# Voltage_Translator.net
KiCad netlist of a schematic drawn in Altium Designer
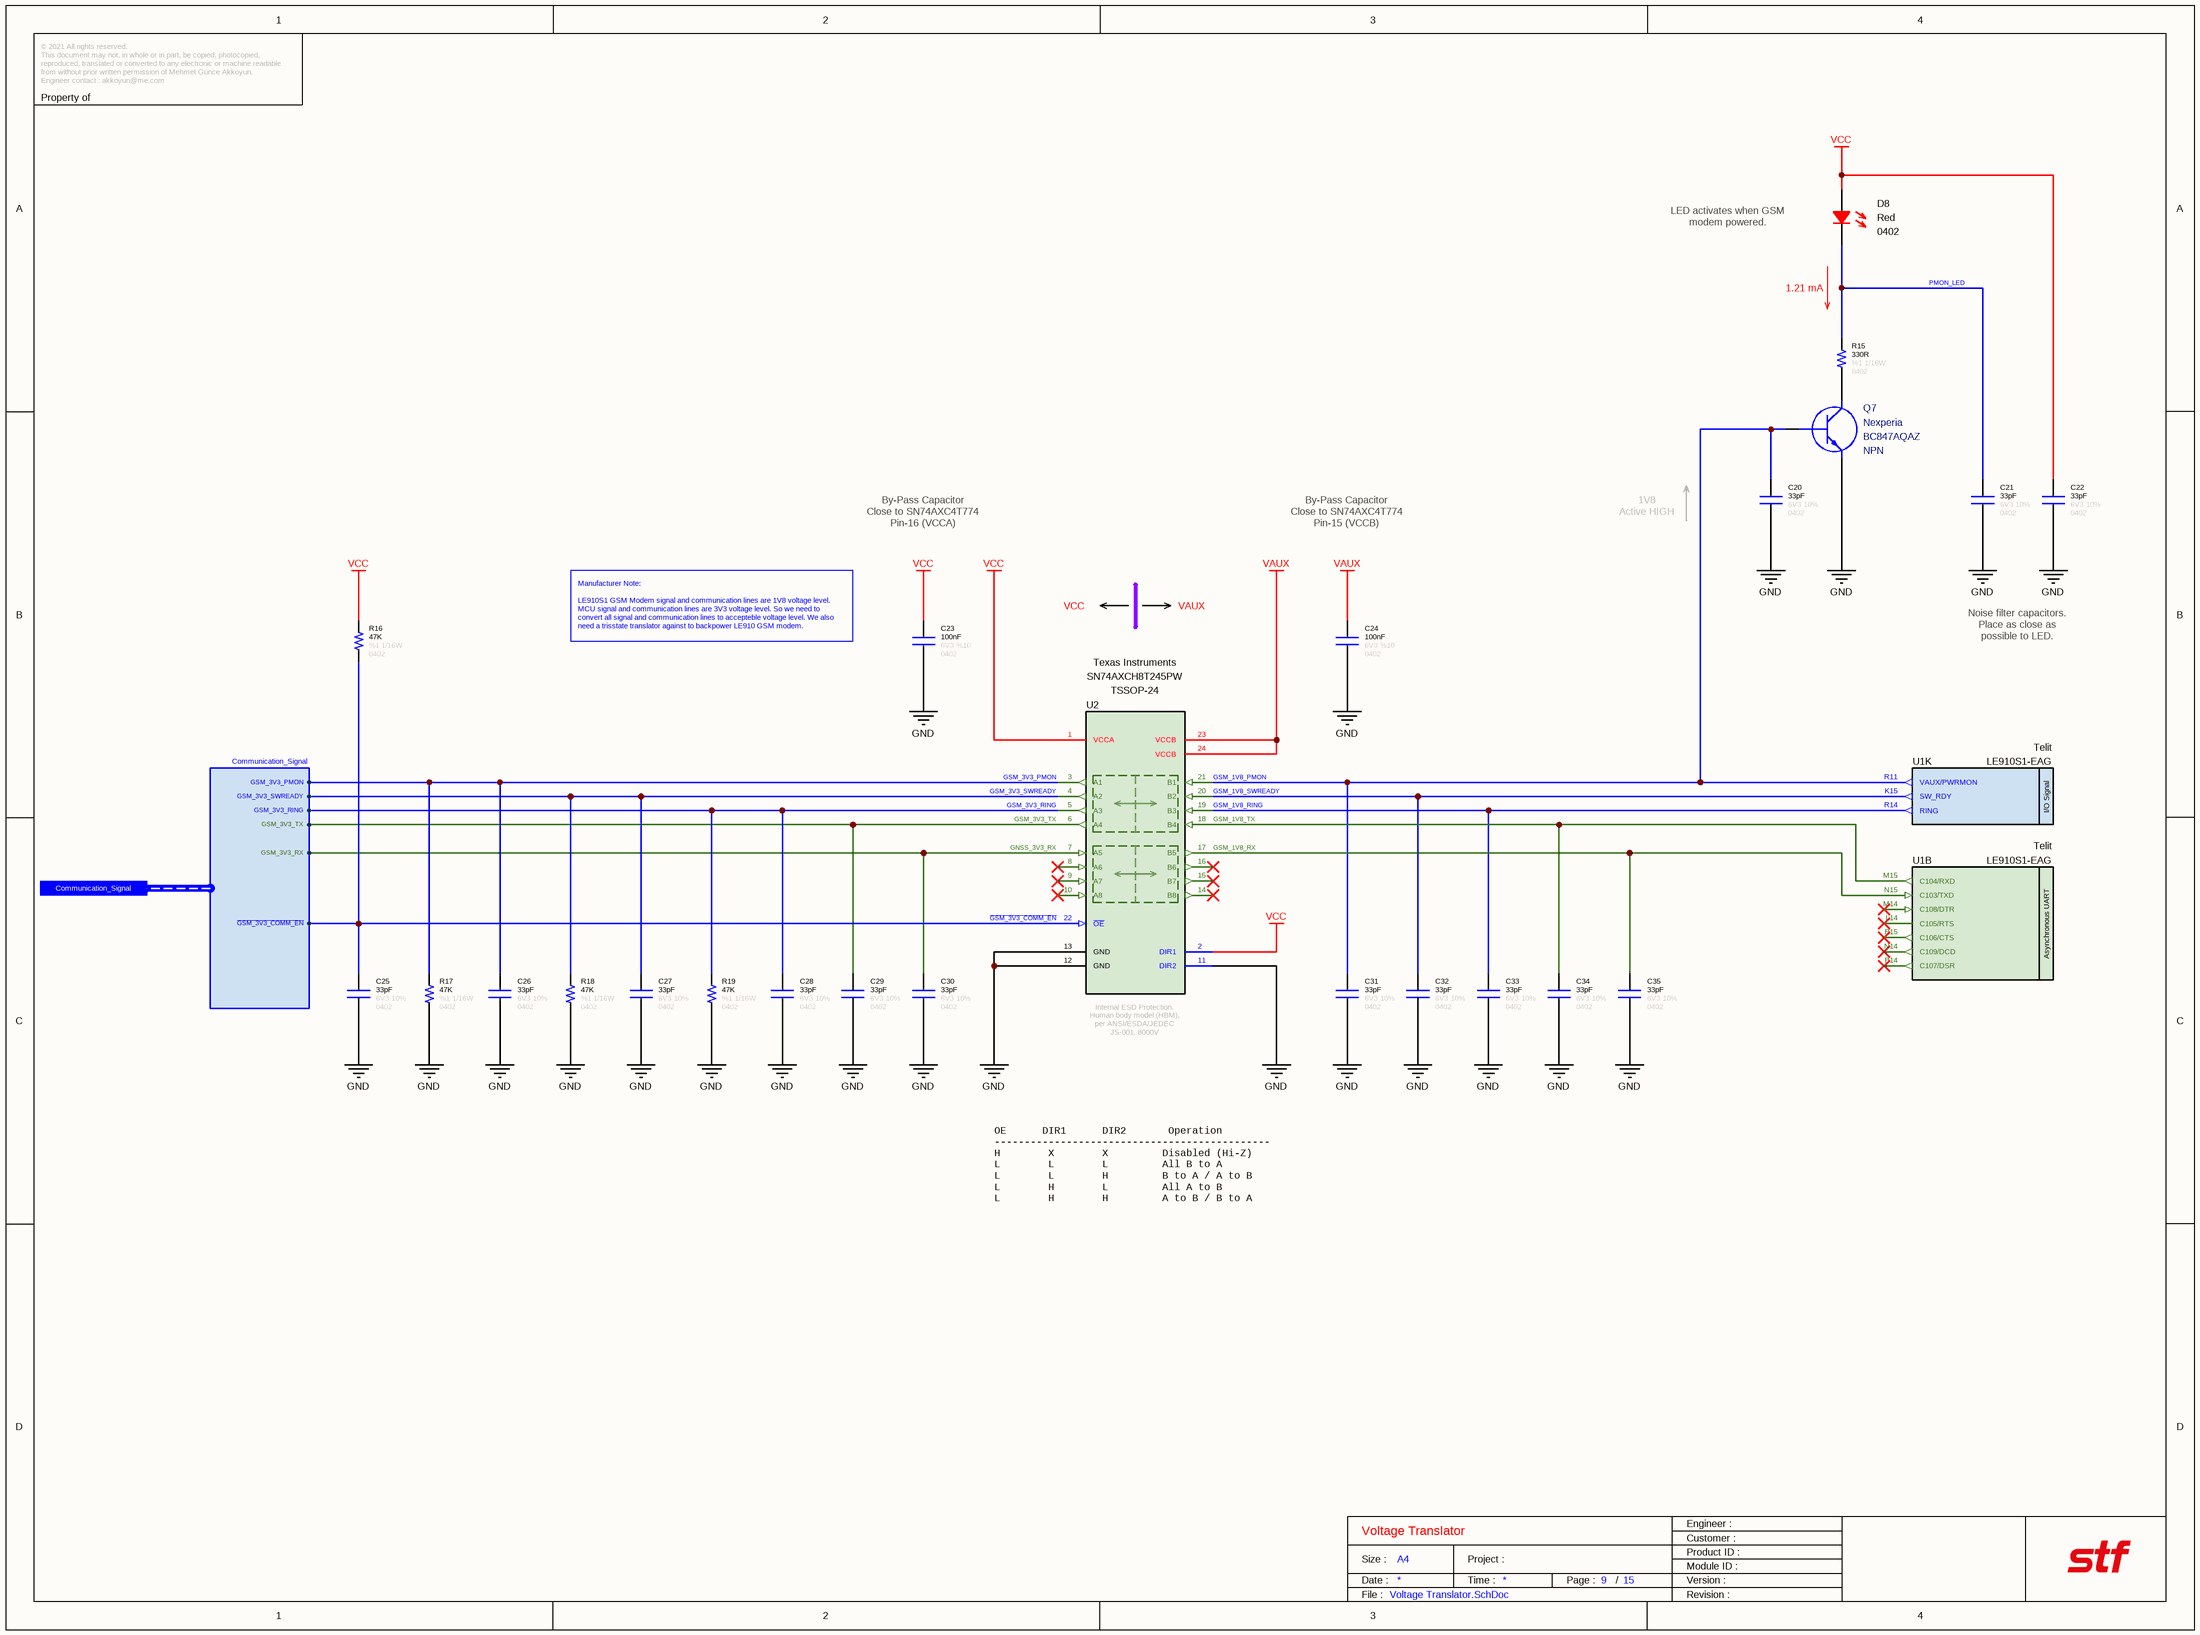
[diagram p0: Voltage Translator.SchDoc]

(export (version "E")
  (design (tool "Eeschema 10.0.6"))
  (components
    (comp (ref "C20")
      (value "33pF")
      (footprint "CAPACITOR_0402")
      (description "Capacitor - 33pF [0402] (Ceramic)")
      (fields
        (field (name "MANUFACTURER PART NUMBER") "C0402C330J9RACAUTO")
        (field (name "TOLERANCE") "10%")
        (field (name "CASE") "0402")
        (field (name "VOLTAGE") "6V3")
      )
      (libsource (lib "P101DA_Library") (part "Capacitor - 33pF [0402-6V3]"))
    )
    (comp (ref "C21")
      (value "33pF")
      (footprint "CAPACITOR_0402")
      (description "Capacitor - 33pF [0402] (Ceramic)")
      (fields
        (field (name "MANUFACTURER PART NUMBER") "C0402C330J9RACAUTO")
        (field (name "TOLERANCE") "10%")
        (field (name "CASE") "0402")
        (field (name "VOLTAGE") "6V3")
      )
      (libsource (lib "P101DA_Library") (part "Capacitor - 33pF [0402-6V3]"))
    )
    (comp (ref "C22")
      (value "33pF")
      (footprint "CAPACITOR_0402")
      (description "Capacitor - 33pF [0402] (Ceramic)")
      (fields
        (field (name "MANUFACTURER PART NUMBER") "C0402C330J9RACAUTO")
        (field (name "TOLERANCE") "10%")
        (field (name "CASE") "0402")
        (field (name "VOLTAGE") "6V3")
      )
      (libsource (lib "P101DA_Library") (part "Capacitor - 33pF [0402-6V3]"))
    )
    (comp (ref "C23")
      (value "100nF")
      (footprint "CAPACITOR_0402")
      (description "Capacitor - 100nF [0402-6V3] (Ceramic)")
      (fields
        (field (name "MANUFACTURER PART NUMBER") "04026D104KAT4A")
        (field (name "TOLERANCE") "%10")
        (field (name "VOLTAGE") "6V3")
        (field (name "CASE") "0402")
        (field (name "Comment") "Capacitor - 100nF [0402] (Ceramic)")
      )
      (libsource (lib "P101DA_Library") (part "Capacitor - 100nF [0402-6V3]"))
    )
    (comp (ref "C24")
      (value "100nF")
      (footprint "CAPACITOR_0402")
      (description "Capacitor - 100nF [0402-6V3] (Ceramic)")
      (fields
        (field (name "MANUFACTURER PART NUMBER") "04026D104KAT4A")
        (field (name "TOLERANCE") "%10")
        (field (name "VOLTAGE") "6V3")
        (field (name "CASE") "0402")
        (field (name "Comment") "Capacitor - 100nF [0402] (Ceramic)")
      )
      (libsource (lib "P101DA_Library") (part "Capacitor - 100nF [0402-6V3]"))
    )
    (comp (ref "C25")
      (value "33pF")
      (footprint "CAPACITOR_0402")
      (description "Capacitor - 33pF [0402] (Ceramic)")
      (fields
        (field (name "MANUFACTURER PART NUMBER") "C0402C330J9RACAUTO")
        (field (name "TOLERANCE") "10%")
        (field (name "CASE") "0402")
        (field (name "VOLTAGE") "6V3")
      )
      (libsource (lib "P101DA_Library") (part "Capacitor - 33pF [0402-6V3]"))
    )
    (comp (ref "C26")
      (value "33pF")
      (footprint "CAPACITOR_0402")
      (description "Capacitor - 33pF [0402] (Ceramic)")
      (fields
        (field (name "MANUFACTURER PART NUMBER") "C0402C330J9RACAUTO")
        (field (name "TOLERANCE") "10%")
        (field (name "CASE") "0402")
        (field (name "VOLTAGE") "6V3")
      )
      (libsource (lib "P101DA_Library") (part "Capacitor - 33pF [0402-6V3]"))
    )
    (comp (ref "C27")
      (value "33pF")
      (footprint "CAPACITOR_0402")
      (description "Capacitor - 33pF [0402] (Ceramic)")
      (fields
        (field (name "MANUFACTURER PART NUMBER") "C0402C330J9RACAUTO")
        (field (name "TOLERANCE") "10%")
        (field (name "CASE") "0402")
        (field (name "VOLTAGE") "6V3")
      )
      (libsource (lib "P101DA_Library") (part "Capacitor - 33pF [0402-6V3]"))
    )
    (comp (ref "C28")
      (value "33pF")
      (footprint "CAPACITOR_0402")
      (description "Capacitor - 33pF [0402] (Ceramic)")
      (fields
        (field (name "MANUFACTURER PART NUMBER") "C0402C330J9RACAUTO")
        (field (name "TOLERANCE") "10%")
        (field (name "CASE") "0402")
        (field (name "VOLTAGE") "6V3")
      )
      (libsource (lib "P101DA_Library") (part "Capacitor - 33pF [0402-6V3]"))
    )
    (comp (ref "C29")
      (value "33pF")
      (footprint "CAPACITOR_0402")
      (description "Capacitor - 33pF [0402] (Ceramic)")
      (fields
        (field (name "MANUFACTURER PART NUMBER") "C0402C330J9RACAUTO")
        (field (name "TOLERANCE") "10%")
        (field (name "CASE") "0402")
        (field (name "VOLTAGE") "6V3")
      )
      (libsource (lib "P101DA_Library") (part "Capacitor - 33pF [0402-6V3]"))
    )
    (comp (ref "C30")
      (value "33pF")
      (footprint "CAPACITOR_0402")
      (description "Capacitor - 33pF [0402] (Ceramic)")
      (fields
        (field (name "MANUFACTURER PART NUMBER") "C0402C330J9RACAUTO")
        (field (name "TOLERANCE") "10%")
        (field (name "CASE") "0402")
        (field (name "VOLTAGE") "6V3")
      )
      (libsource (lib "P101DA_Library") (part "Capacitor - 33pF [0402-6V3]"))
    )
    (comp (ref "C31")
      (value "33pF")
      (footprint "CAPACITOR_0402")
      (description "Capacitor - 33pF [0402] (Ceramic)")
      (fields
        (field (name "MANUFACTURER PART NUMBER") "C0402C330J9RACAUTO")
        (field (name "TOLERANCE") "10%")
        (field (name "CASE") "0402")
        (field (name "VOLTAGE") "6V3")
      )
      (libsource (lib "P101DA_Library") (part "Capacitor - 33pF [0402-6V3]"))
    )
    (comp (ref "C32")
      (value "33pF")
      (footprint "CAPACITOR_0402")
      (description "Capacitor - 33pF [0402] (Ceramic)")
      (fields
        (field (name "MANUFACTURER PART NUMBER") "C0402C330J9RACAUTO")
        (field (name "TOLERANCE") "10%")
        (field (name "CASE") "0402")
        (field (name "VOLTAGE") "6V3")
      )
      (libsource (lib "P101DA_Library") (part "Capacitor - 33pF [0402-6V3]"))
    )
    (comp (ref "C33")
      (value "33pF")
      (footprint "CAPACITOR_0402")
      (description "Capacitor - 33pF [0402] (Ceramic)")
      (fields
        (field (name "MANUFACTURER PART NUMBER") "C0402C330J9RACAUTO")
        (field (name "TOLERANCE") "10%")
        (field (name "CASE") "0402")
        (field (name "VOLTAGE") "6V3")
      )
      (libsource (lib "P101DA_Library") (part "Capacitor - 33pF [0402-6V3]"))
    )
    (comp (ref "C34")
      (value "33pF")
      (footprint "CAPACITOR_0402")
      (description "Capacitor - 33pF [0402] (Ceramic)")
      (fields
        (field (name "MANUFACTURER PART NUMBER") "C0402C330J9RACAUTO")
        (field (name "TOLERANCE") "10%")
        (field (name "CASE") "0402")
        (field (name "VOLTAGE") "6V3")
      )
      (libsource (lib "P101DA_Library") (part "Capacitor - 33pF [0402-6V3]"))
    )
    (comp (ref "C35")
      (value "33pF")
      (footprint "CAPACITOR_0402")
      (description "Capacitor - 33pF [0402] (Ceramic)")
      (fields
        (field (name "MANUFACTURER PART NUMBER") "C0402C330J9RACAUTO")
        (field (name "TOLERANCE") "10%")
        (field (name "CASE") "0402")
        (field (name "VOLTAGE") "6V3")
      )
      (libsource (lib "P101DA_Library") (part "Capacitor - 33pF [0402-6V3]"))
    )
    (comp (ref "D8")
      (value "SMD LED (Red)")
      (footprint "LED_0402")
      (description "Standard LEDs - SMD MINI-MOLD ULTRA COMPACT RED")
      (fields
        (field (name "MANUFACTURER PART NUMBER") "SML-P12VTT86R")
        (field (name "CASE") "0402")
        (field (name "COLOR") "Red")
      )
      (libsource (lib "P101DA_Library") (part "Diode - LED (0402-Red)"))
    )
    (comp (ref "Q7")
      (value "BC847AQAZ")
      (footprint "SOT1215")
      (description "Bipolar NPN Transistors")
      (fields
        (field (name "MANUFACTURER NAME") "Nexperia")
        (field (name "MANUFACTURER PART NUMBER") "BC847AQAZ")
        (field (name "POLARITY") "NPN")
      )
      (libsource (lib "P101DA_Library") (part "Transistor - BC847"))
    )
    (comp (ref "R15")
      (value "330R")
      (footprint "RESISTOR_0402")
      (description "Thick Film Resistors - SMD 1/16 W 330 Ohm 1%")
      (fields
        (field (name "MANUFACTURER PART NUMBER") "CRCW0402330RFKED")
        (field (name "CASE") "0402")
        (field (name "TOLERANCE") "%1")
        (field (name "POWER") "1/16W")
        (field (name "Comment") "330R - 0402 - %1 - 1/16W")
      )
      (libsource (lib "P101DA_Library") (part "Resistor - 330R [0402]"))
    )
    (comp (ref "R16")
      (value "47K")
      (footprint "RESISTOR_0402")
      (description "Thick Film Resistors - SMD 1/16 W 47 KOhm 1%")
      (fields
        (field (name "MANUFACTURER PART NUMBER") "CRCW040247K0FKED")
        (field (name "TOLERANCE") "%1")
        (field (name "CASE") "0402")
        (field (name "POWER") "1/16W")
        (field (name "Comment") "47K - 0402 - %1 - 1/16W")
      )
      (libsource (lib "P101DA_Library") (part "Resistor - 47K [0402]"))
    )
    (comp (ref "R17")
      (value "47K")
      (footprint "RESISTOR_0402")
      (description "Thick Film Resistors - SMD 1/16 W 47 KOhm 1%")
      (fields
        (field (name "MANUFACTURER PART NUMBER") "CRCW040247K0FKED")
        (field (name "TOLERANCE") "%1")
        (field (name "CASE") "0402")
        (field (name "POWER") "1/16W")
        (field (name "Comment") "47K - 0402 - %1 - 1/16W")
      )
      (libsource (lib "P101DA_Library") (part "Resistor - 47K [0402]"))
    )
    (comp (ref "R18")
      (value "47K")
      (footprint "RESISTOR_0402")
      (description "Thick Film Resistors - SMD 1/16 W 47 KOhm 1%")
      (fields
        (field (name "MANUFACTURER PART NUMBER") "CRCW040247K0FKED")
        (field (name "TOLERANCE") "%1")
        (field (name "CASE") "0402")
        (field (name "POWER") "1/16W")
        (field (name "Comment") "47K - 0402 - %1 - 1/16W")
      )
      (libsource (lib "P101DA_Library") (part "Resistor - 47K [0402]"))
    )
    (comp (ref "R19")
      (value "47K")
      (footprint "RESISTOR_0402")
      (description "Thick Film Resistors - SMD 1/16 W 47 KOhm 1%")
      (fields
        (field (name "MANUFACTURER PART NUMBER") "CRCW040247K0FKED")
        (field (name "TOLERANCE") "%1")
        (field (name "CASE") "0402")
        (field (name "POWER") "1/16W")
        (field (name "Comment") "47K - 0402 - %1 - 1/16W")
      )
      (libsource (lib "P101DA_Library") (part "Resistor - 47K [0402]"))
    )
    (comp (ref "U1")
      (value "LE910S1-EAG LTE GSM Module")
      (footprint "LE910 GSM Modem")
      (description "Telit LE910S1-EAG GPRS/GNSS Module")
      (fields
        (field (name "MANUFACTURER PART NUMBER") "LE910S1-EAG")
        (field (name "MANUFACTURER NAME") "Telit")
      )
      (libsource (lib "P101DA_Library") (part "IC - LE910S1-EAG"))
    )
    (comp (ref "U2")
      (value "SN74AXCH8T245PW")
      (footprint "TSSOP-24")
      (description "Translation - Voltage Levels 8-Bit Dual-Supply Bus Transceiver 24-TSSOP -40 to 125")
      (fields
        (field (name "MANUFACTURER NAME") "Texas Instruments")
        (field (name "MANUFACTURER PART NUMBER") "SN74AXCH8T245PW")
        (field (name "CASE") "TSSOP-24")
      )
      (libsource (lib "P101DA_Library") (part "IC - SN74AXCH8T245PW"))
    )
  )
  (nets
    (net (code "2") (name "/GNSS_3V3_RX") (class "Default")
      (node (ref "C30") (pin "2") (pinfunction "2_2") (pintype "passive"))
      (node (ref "U2") (pin "7") (pinfunction "A5_7") (pintype "input"))
    )
    (net (code "3") (name "/GSM_1V8_PMON") (class "Default")
      (node (ref "C20") (pin "2") (pinfunction "2_2") (pintype "passive"))
      (node (ref "C31") (pin "2") (pinfunction "2_2") (pintype "passive"))
      (node (ref "Q7") (pin "1") (pinfunction "B_1") (pintype "passive"))
      (node (ref "U1") (pin "R11") (pinfunction "VAUX/PWRMON_R11") (pintype "output"))
      (node (ref "U2") (pin "21") (pinfunction "B1_21") (pintype "input"))
    )
    (net (code "4") (name "/GSM_1V8_RING") (class "Default")
      (node (ref "C33") (pin "2") (pinfunction "2_2") (pintype "passive"))
      (node (ref "U1") (pin "R14") (pinfunction "RING_R14") (pintype "output"))
      (node (ref "U2") (pin "19") (pinfunction "B3_19") (pintype "input"))
    )
    (net (code "5") (name "/GSM_1V8_RX") (class "Default")
      (node (ref "C35") (pin "2") (pinfunction "2_2") (pintype "passive"))
      (node (ref "U1") (pin "N15") (pinfunction "C103/TXD_N15") (pintype "input"))
      (node (ref "U2") (pin "17") (pinfunction "B5_17") (pintype "output"))
    )
    (net (code "6") (name "/GSM_1V8_SWREADY") (class "Default")
      (node (ref "C32") (pin "2") (pinfunction "2_2") (pintype "passive"))
      (node (ref "U1") (pin "K15") (pinfunction "SW_RDY_K15") (pintype "output"))
      (node (ref "U2") (pin "20") (pinfunction "B2_20") (pintype "input"))
    )
    (net (code "7") (name "/GSM_1V8_TX") (class "Default")
      (node (ref "C34") (pin "2") (pinfunction "2_2") (pintype "passive"))
      (node (ref "U1") (pin "M15") (pinfunction "C104/RXD_M15") (pintype "output"))
      (node (ref "U2") (pin "18") (pinfunction "B4_18") (pintype "input"))
    )
    (net (code "8") (name "/GSM_3V3_PMON") (class "Default")
      (node (ref "C26") (pin "2") (pinfunction "2_2") (pintype "passive"))
      (node (ref "R17") (pin "2") (pinfunction "2_2") (pintype "passive"))
      (node (ref "U2") (pin "3") (pinfunction "A1_3") (pintype "output"))
    )
    (net (code "9") (name "/GSM_3V3_RING") (class "Default")
      (node (ref "C28") (pin "2") (pinfunction "2_2") (pintype "passive"))
      (node (ref "R19") (pin "2") (pinfunction "2_2") (pintype "passive"))
      (node (ref "U2") (pin "5") (pinfunction "A3_5") (pintype "output"))
    )
    (net (code "10") (name "/GSM_3V3_SWREADY") (class "Default")
      (node (ref "C27") (pin "2") (pinfunction "2_2") (pintype "passive"))
      (node (ref "R18") (pin "2") (pinfunction "2_2") (pintype "passive"))
      (node (ref "U2") (pin "4") (pinfunction "A2_4") (pintype "output"))
    )
    (net (code "11") (name "/GSM_3V3_TX") (class "Default")
      (node (ref "C29") (pin "2") (pinfunction "2_2") (pintype "passive"))
      (node (ref "U2") (pin "6") (pinfunction "A4_6") (pintype "output"))
    )
    (net (code "12") (name "/PMON_LED") (class "Default")
      (node (ref "C21") (pin "2") (pinfunction "2_2") (pintype "passive"))
      (node (ref "D8") (pin "1") (pinfunction "1_1") (pintype "passive"))
      (node (ref "R15") (pin "2") (pinfunction "2_2") (pintype "passive"))
    )
    (net (code "14") (name "/~{GSM_3V3_COMM_EN}") (class "Default")
      (node (ref "C25") (pin "2") (pinfunction "2_2") (pintype "passive"))
      (node (ref "R16") (pin "1") (pinfunction "1_1") (pintype "passive"))
      (node (ref "U2") (pin "22") (pinfunction "~{OE}_22") (pintype "input"))
    )
    (net (code "15") (name "GND") (class "Default")
      (node (ref "C20") (pin "1") (pinfunction "1_1") (pintype "passive"))
      (node (ref "C21") (pin "1") (pinfunction "1_1") (pintype "passive"))
      (node (ref "C22") (pin "1") (pinfunction "1_1") (pintype "passive"))
      (node (ref "C23") (pin "1") (pinfunction "1_1") (pintype "passive"))
      (node (ref "C24") (pin "1") (pinfunction "1_1") (pintype "passive"))
      (node (ref "C25") (pin "1") (pinfunction "1_1") (pintype "passive"))
      (node (ref "C26") (pin "1") (pinfunction "1_1") (pintype "passive"))
      (node (ref "C27") (pin "1") (pinfunction "1_1") (pintype "passive"))
      (node (ref "C28") (pin "1") (pinfunction "1_1") (pintype "passive"))
      (node (ref "C29") (pin "1") (pinfunction "1_1") (pintype "passive"))
      (node (ref "C30") (pin "1") (pinfunction "1_1") (pintype "passive"))
      (node (ref "C31") (pin "1") (pinfunction "1_1") (pintype "passive"))
      (node (ref "C32") (pin "1") (pinfunction "1_1") (pintype "passive"))
      (node (ref "C33") (pin "1") (pinfunction "1_1") (pintype "passive"))
      (node (ref "C34") (pin "1") (pinfunction "1_1") (pintype "passive"))
      (node (ref "C35") (pin "1") (pinfunction "1_1") (pintype "passive"))
      (node (ref "Q7") (pin "2") (pinfunction "E_2") (pintype "passive"))
      (node (ref "R17") (pin "1") (pinfunction "1_1") (pintype "passive"))
      (node (ref "R18") (pin "1") (pinfunction "1_1") (pintype "passive"))
      (node (ref "R19") (pin "1") (pinfunction "1_1") (pintype "passive"))
      (node (ref "U2") (pin "11") (pinfunction "DIR2_11") (pintype "passive"))
      (node (ref "U2") (pin "12") (pinfunction "GND_12") (pintype "power_in"))
      (node (ref "U2") (pin "13") (pinfunction "GND_13") (pintype "power_in"))
    )
    (net (code "16") (name "Net-(Q7-C)") (class "Default")
      (node (ref "Q7") (pin "3") (pinfunction "C_3") (pintype "passive"))
      (node (ref "R15") (pin "1") (pinfunction "1_1") (pintype "passive"))
    )
    (net (code "17") (name "VAUX") (class "Default")
      (node (ref "C24") (pin "2") (pinfunction "2_2") (pintype "passive"))
      (node (ref "U2") (pin "23") (pinfunction "VCCB_23") (pintype "power_in"))
      (node (ref "U2") (pin "24") (pinfunction "VCCB_24") (pintype "power_in"))
    )
    (net (code "18") (name "VCC") (class "Default")
      (node (ref "C22") (pin "2") (pinfunction "2_2") (pintype "passive"))
      (node (ref "C23") (pin "2") (pinfunction "2_2") (pintype "passive"))
      (node (ref "D8") (pin "2") (pinfunction "2_2") (pintype "passive"))
      (node (ref "R16") (pin "2") (pinfunction "2_2") (pintype "passive"))
      (node (ref "U2") (pin "1") (pinfunction "VCCA_1") (pintype "power_in"))
      (node (ref "U2") (pin "2") (pinfunction "DIR1_2") (pintype "passive"))
    )
    (net (code "19") (name "unconnected-(U1B-C105{slash}RTS-PadL14)") (class "Default")
      (node (ref "U1") (pin "L14") (pinfunction "C105/RTS_L14") (pintype "open_collector+no_connect"))
    )
    (net (code "20") (name "unconnected-(U1B-C106{slash}CTS-PadP15)") (class "Default")
      (node (ref "U1") (pin "P15") (pinfunction "C106/CTS_P15") (pintype "output+no_connect"))
    )
    (net (code "21") (name "unconnected-(U1B-C107{slash}DSR-PadP14)") (class "Default")
      (node (ref "U1") (pin "P14") (pinfunction "C107/DSR_P14") (pintype "output+no_connect"))
    )
    (net (code "22") (name "unconnected-(U1B-C108{slash}DTR-PadM14)") (class "Default")
      (node (ref "U1") (pin "M14") (pinfunction "C108/DTR_M14") (pintype "input+no_connect"))
    )
    (net (code "23") (name "unconnected-(U1B-C109{slash}DCD-PadN14)") (class "Default")
      (node (ref "U1") (pin "N14") (pinfunction "C109/DCD_N14") (pintype "output+no_connect"))
    )
    (net (code "24") (name "unconnected-(U2-A6-Pad8)") (class "Default")
      (node (ref "U2") (pin "8") (pinfunction "A6_8") (pintype "input+no_connect"))
    )
    (net (code "25") (name "unconnected-(U2-A7-Pad9)") (class "Default")
      (node (ref "U2") (pin "9") (pinfunction "A7_9") (pintype "input+no_connect"))
    )
    (net (code "26") (name "unconnected-(U2-A8-Pad10)") (class "Default")
      (node (ref "U2") (pin "10") (pinfunction "A8_10") (pintype "input+no_connect"))
    )
    (net (code "27") (name "unconnected-(U2-B6-Pad16)") (class "Default")
      (node (ref "U2") (pin "16") (pinfunction "B6_16") (pintype "output+no_connect"))
    )
    (net (code "28") (name "unconnected-(U2-B7-Pad15)") (class "Default")
      (node (ref "U2") (pin "15") (pinfunction "B7_15") (pintype "output+no_connect"))
    )
    (net (code "29") (name "unconnected-(U2-B8-Pad14)") (class "Default")
      (node (ref "U2") (pin "14") (pinfunction "B8_14") (pintype "output+no_connect"))
    )
  )
)
